# pidplate-mk-1.net
KiCad netlist of a schematic drawn in EAGLE
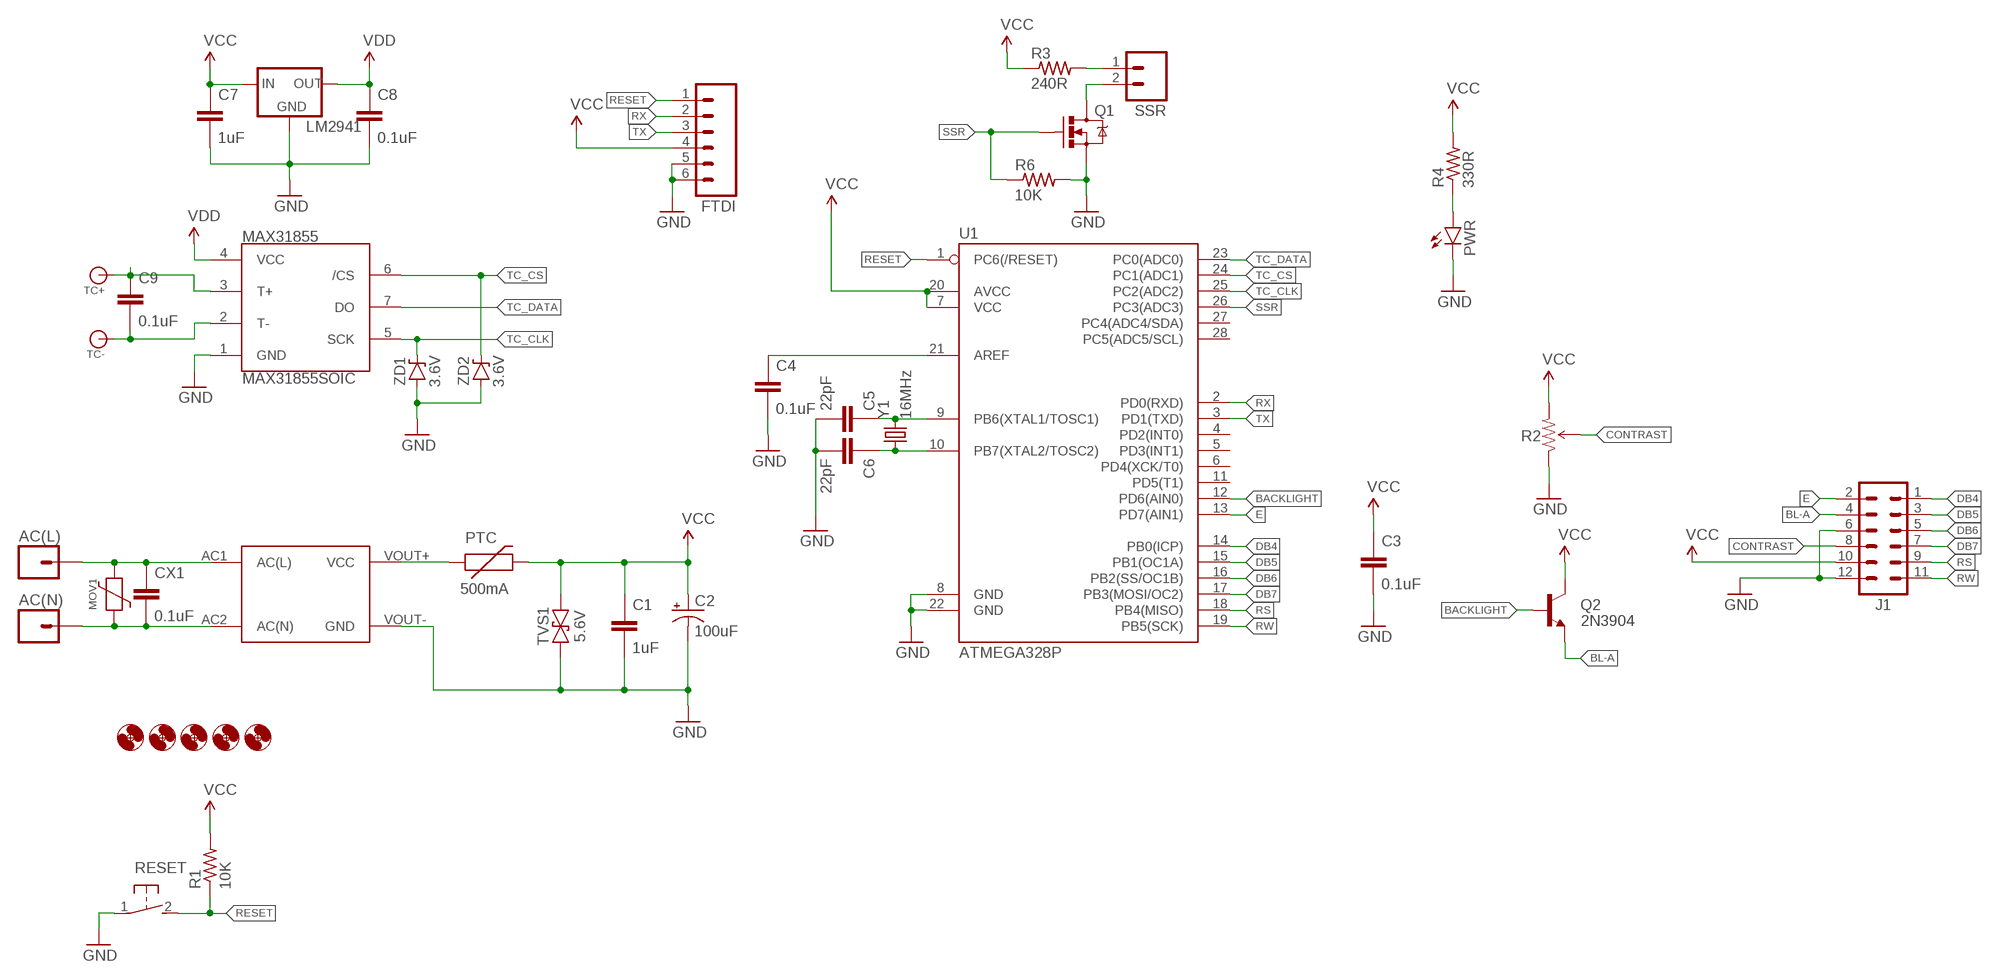
[diagram p0: schematic, sheet 1]

(export (version "E")
  (design (tool "Eeschema 10.0.6"))
  (components
    (comp (ref "AC(L)")
      (value "M01PTH-1.2MM")
      (footprint "eagle-import:1X01-1.2MM")
      (libsource (lib "eagle-import") (part "M01PTH-1.2MM"))
    )
    (comp (ref "AC(N)")
      (value "M01PTH-1.2MM")
      (footprint "eagle-import:1X01-1.2MM")
      (libsource (lib "eagle-import") (part "M01PTH-1.2MM"))
    )
    (comp (ref "C1")
      (value "1uF")
      (footprint "eagle-import:C025-024X044")
      (libsource (lib "eagle-import") (part "CAPACITOR-CERAMIC025-024X044"))
    )
    (comp (ref "C2")
      (value "100uF")
      (footprint "eagle-import:E2,5-7")
      (libsource (lib "eagle-import") (part "CAPACITOR-POLARIZEDE2.5-7"))
    )
    (comp (ref "C3")
      (value "0.1uF")
      (footprint "eagle-import:C025-024X044")
      (libsource (lib "eagle-import") (part "CAPACITOR-CERAMIC025-024X044"))
    )
    (comp (ref "C4")
      (value "0.1uF")
      (footprint "eagle-import:C025-024X044")
      (libsource (lib "eagle-import") (part "CAPACITOR-CERAMIC025-024X044"))
    )
    (comp (ref "C5")
      (value "22pF")
      (footprint "eagle-import:C025-024X044")
      (libsource (lib "eagle-import") (part "CAPACITOR-CERAMIC025-024X044"))
    )
    (comp (ref "C6")
      (value "22pF")
      (footprint "eagle-import:C025-024X044")
      (libsource (lib "eagle-import") (part "CAPACITOR-CERAMIC025-024X044"))
    )
    (comp (ref "C7")
      (value "1uF")
      (footprint "eagle-import:C025-024X044")
      (libsource (lib "eagle-import") (part "CAPACITOR-CERAMIC025-024X044"))
    )
    (comp (ref "C8")
      (value "0.1uF")
      (footprint "eagle-import:C025-024X044")
      (libsource (lib "eagle-import") (part "CAPACITOR-CERAMIC025-024X044"))
    )
    (comp (ref "C9")
      (value "0.1uF")
      (footprint "eagle-import:C025-024X044")
      (libsource (lib "eagle-import") (part "CAPACITOR-CERAMIC025-024X044"))
    )
    (comp (ref "CX1")
      (value "0.1uF")
      (footprint "eagle-import:XC10B5")
      (libsource (lib "eagle-import") (part "CXXC10B5"))
    )
    (comp (ref "FTDI")
      (value "M06SIP")
      (footprint "eagle-import:1X06")
      (libsource (lib "eagle-import") (part "M06SIP"))
    )
    (comp (ref "H1")
      (value "HOLE#2")
      (footprint "eagle-import:HOLE-#2")
      (libsource (lib "eagle-import") (part "HOLE#2"))
    )
    (comp (ref "H2")
      (value "HOLE#2")
      (footprint "eagle-import:HOLE-#2")
      (libsource (lib "eagle-import") (part "HOLE#2"))
    )
    (comp (ref "H3")
      (value "HOLE#2")
      (footprint "eagle-import:HOLE-#2")
      (libsource (lib "eagle-import") (part "HOLE#2"))
    )
    (comp (ref "H4")
      (value "HOLE#2")
      (footprint "eagle-import:HOLE-#2")
      (libsource (lib "eagle-import") (part "HOLE#2"))
    )
    (comp (ref "H5")
      (value "HOLE#2")
      (footprint "eagle-import:HOLE-#2")
      (libsource (lib "eagle-import") (part "HOLE#2"))
    )
    (comp (ref "J1")
      (value "M06X2PTH")
      (footprint "eagle-import:2X6_PTH")
      (libsource (lib "eagle-import") (part "M06X2PTH"))
    )
    (comp (ref "LM2941")
      (value "L2941")
      (footprint "eagle-import:TO-92-AMMO")
      (libsource (lib "eagle-import") (part "V_REG_78XXTO-92-INLINE"))
    )
    (comp (ref "MAX31855")
      (value "MAX31855SOIC")
      (footprint "eagle-import:SOIC127P600X175-8N")
      (libsource (lib "eagle-import") (part "MAX31855SOIC"))
    )
    (comp (ref "MOV1")
      (value "VARISITORVAR-5.08MM-PTH")
      (footprint "eagle-import:VAR-5.08MM-PTH")
      (libsource (lib "eagle-import") (part "VARISITORVAR-5.08MM-PTH"))
    )
    (comp (ref "PTC")
      (value "500mA")
      (footprint "eagle-import:PTC")
      (libsource (lib "eagle-import") (part "PTCPTH"))
    )
    (comp (ref "PWR")
      (value "LED3MM")
      (footprint "eagle-import:LED3MM")
      (libsource (lib "eagle-import") (part "LED3MM"))
    )
    (comp (ref "Q1")
      (value "2N7000")
      (footprint "eagle-import:TO-92-AMMO")
      (libsource (lib "eagle-import") (part "MOSFET-NCHANNEL2N7000-AMMO"))
    )
    (comp (ref "Q2")
      (value "2N3904")
      (footprint "eagle-import:TO-92-AMMO")
      (libsource (lib "eagle-import") (part "TRANSISTOR_NPNTO-92-AMMO-CBE"))
    )
    (comp (ref "R1")
      (value "10K")
      (footprint "eagle-import:RESISTOR-AXIAL-PTH-5.08MM")
      (libsource (lib "eagle-import") (part "RESISTORPTH-AXIAL-5.08MM"))
    )
    (comp (ref "R2")
      (value "20K")
      (footprint "eagle-import:TRIM_POT_PTH")
      (libsource (lib "eagle-import") (part "TRIMPOTPTH"))
    )
    (comp (ref "R3")
      (value "240R")
      (footprint "eagle-import:RESISTOR-AXIAL-PTH-6.35MM")
      (libsource (lib "eagle-import") (part "RESISTORPTH-AXIAL-6.35MM"))
    )
    (comp (ref "R4")
      (value "330R")
      (footprint "eagle-import:RESISTOR-AXIAL-PTH-5.08MM")
      (libsource (lib "eagle-import") (part "RESISTORPTH-AXIAL-5.08MM"))
    )
    (comp (ref "R6")
      (value "10K")
      (footprint "eagle-import:RESISTOR-AXIAL-PTH-6.35MM")
      (libsource (lib "eagle-import") (part "RESISTORPTH-AXIAL-6.35MM"))
    )
    (comp (ref "RESET")
      (value "SPST-NO-TACT3MM-RA")
      (footprint "eagle-import:TACTILE-PTH-SIDE")
      (libsource (lib "eagle-import") (part "SPST-NO-TACT3MM-RA"))
    )
    (comp (ref "SSR")
      (value "M02JST-PTH-VERT")
      (footprint "eagle-import:JST-2-PH-VERT-PTH")
      (libsource (lib "eagle-import") (part "M02JST-PTH-VERT"))
    )
    (comp (ref "TC+")
      (value "BANANA_CONNPTH-RA")
      (footprint "eagle-import:BANANA-PTH-RA-SAFEWORD")
      (libsource (lib "eagle-import") (part "BANANA_CONNPTH-RA"))
    )
    (comp (ref "TC-")
      (value "BANANA_CONNPTH-RA")
      (footprint "eagle-import:BANANA-PTH-RA-SAFEWORD")
      (libsource (lib "eagle-import") (part "BANANA_CONNPTH-RA"))
    )
    (comp (ref "TVS1")
      (value "5.6V")
      (footprint "eagle-import:DO-41-TVS")
      (libsource (lib "eagle-import") (part "TVSDO-41-TVS-BIDIRECTIONAL"))
    )
    (comp (ref "U1")
      (value "ATMEGA328P")
      (footprint "eagle-import:DIL28-3")
      (libsource (lib "eagle-import") (part "ATMEGA328P_PDIP"))
    )
    (comp (ref "U3")
      (value "VSK-S1")
      (footprint "eagle-import:VSK-S1")
      (libsource (lib "eagle-import") (part "VSK-S1"))
    )
    (comp (ref "Y1")
      (value "16MHz")
      (footprint "eagle-import:HC49U-V")
      (libsource (lib "eagle-import") (part "CRYSTALHC49UV"))
    )
    (comp (ref "ZD1")
      (value "3.6V")
      (footprint "eagle-import:DIODE-7.68MM")
      (libsource (lib "eagle-import") (part "DIODE-ZENERPTH-7.68MM"))
    )
    (comp (ref "ZD2")
      (value "3.6V")
      (footprint "eagle-import:DIODE-7.68MM")
      (libsource (lib "eagle-import") (part "DIODE-ZENERPTH-7.68MM"))
    )
  )
  (nets
    (net (code "1") (name "BACKLIGHT") (class "Default")
      (node (ref "Q2") (pin "2") (pinfunction "B_2") (pintype "passive"))
      (node (ref "U1") (pin "12") (pinfunction "PD6(AIN0)_12") (pintype "bidirectional"))
    )
    (net (code "2") (name "BL-A") (class "Default")
      (node (ref "J1") (pin "4") (pinfunction "4_4") (pintype "passive"))
      (node (ref "Q2") (pin "3") (pinfunction "E_3") (pintype "passive"))
    )
    (net (code "3") (name "CONTRAST") (class "Default")
      (node (ref "J1") (pin "8") (pinfunction "8_8") (pintype "passive"))
      (node (ref "R2") (pin "2") (pinfunction "WIPER_2") (pintype "passive"))
    )
    (net (code "4") (name "DB4") (class "Default")
      (node (ref "J1") (pin "1") (pinfunction "1_1") (pintype "passive"))
      (node (ref "U1") (pin "14") (pinfunction "PB0(ICP)_14") (pintype "bidirectional"))
    )
    (net (code "5") (name "DB5") (class "Default")
      (node (ref "J1") (pin "3") (pinfunction "3_3") (pintype "passive"))
      (node (ref "U1") (pin "15") (pinfunction "PB1(OC1A)_15") (pintype "bidirectional"))
    )
    (net (code "6") (name "DB6") (class "Default")
      (node (ref "J1") (pin "5") (pinfunction "5_5") (pintype "passive"))
      (node (ref "U1") (pin "16") (pinfunction "PB2(SS/OC1B)_16") (pintype "bidirectional"))
    )
    (net (code "7") (name "DB7") (class "Default")
      (node (ref "J1") (pin "7") (pinfunction "7_7") (pintype "passive"))
      (node (ref "U1") (pin "17") (pinfunction "PB3(MOSI/OC2)_17") (pintype "bidirectional"))
    )
    (net (code "8") (name "E") (class "Default")
      (node (ref "J1") (pin "2") (pinfunction "2_2") (pintype "passive"))
      (node (ref "U1") (pin "13") (pinfunction "PD7(AIN1)_13") (pintype "bidirectional"))
    )
    (net (code "9") (name "GND") (class "Default")
      (node (ref "C1") (pin "2") (pinfunction "2_2") (pintype "passive"))
      (node (ref "C2") (pin "-") (pinfunction "-_-") (pintype "passive"))
      (node (ref "C3") (pin "2") (pinfunction "2_2") (pintype "passive"))
      (node (ref "C4") (pin "2") (pinfunction "2_2") (pintype "passive"))
      (node (ref "C5") (pin "2") (pinfunction "2_2") (pintype "passive"))
      (node (ref "C6") (pin "2") (pinfunction "2_2") (pintype "passive"))
      (node (ref "C7") (pin "2") (pinfunction "2_2") (pintype "passive"))
      (node (ref "C8") (pin "2") (pinfunction "2_2") (pintype "passive"))
      (node (ref "FTDI") (pin "5") (pinfunction "5_5") (pintype "passive"))
      (node (ref "FTDI") (pin "6") (pinfunction "6_6") (pintype "passive"))
      (node (ref "J1") (pin "12") (pinfunction "12_12") (pintype "passive"))
      (node (ref "J1") (pin "6") (pinfunction "6_6") (pintype "passive"))
      (node (ref "LM2941") (pin "2") (pinfunction "GND_2") (pintype "input"))
      (node (ref "MAX31855") (pin "1") (pinfunction "GND_1") (pintype "power_in"))
      (node (ref "PWR") (pin "K") (pinfunction "C_K") (pintype "passive"))
      (node (ref "Q1") (pin "1") (pinfunction "S_1") (pintype "passive"))
      (node (ref "R2") (pin "1") (pinfunction "CCW_1") (pintype "passive"))
      (node (ref "R6") (pin "P$2") (pinfunction "2_P$2") (pintype "passive"))
      (node (ref "RESET") (pin "1") (pinfunction "1_1") (pintype "passive"))
      (node (ref "TVS1") (pin "P$1") (pinfunction "1_P$1") (pintype "passive"))
      (node (ref "U1") (pin "22") (pinfunction "GND_22") (pintype "bidirectional"))
      (node (ref "U1") (pin "8") (pinfunction "GND_8") (pintype "bidirectional"))
      (node (ref "U3") (pin "VOUT-") (pinfunction "GND_VOUT-") (pintype "bidirectional"))
      (node (ref "ZD1") (pin "A") (pinfunction "A_A") (pintype "passive"))
      (node (ref "ZD2") (pin "A") (pinfunction "A_A") (pintype "passive"))
    )
    (net (code "10") (name "Net-(AC(L)-1)") (class "Default")
      (node (ref "AC(L)") (pin "P$1") (pinfunction "1_P$1") (pintype "passive"))
      (node (ref "CX1") (pin "1") (pinfunction "1_1") (pintype "passive"))
      (node (ref "MOV1") (pin "2") (pinfunction "P$2_2") (pintype "bidirectional"))
      (node (ref "U3") (pin "AC1") (pinfunction "AC(L)_AC1") (pintype "bidirectional"))
    )
    (net (code "11") (name "Net-(AC(N)-1)") (class "Default")
      (node (ref "AC(N)") (pin "P$1") (pinfunction "1_P$1") (pintype "passive"))
      (node (ref "CX1") (pin "2") (pinfunction "2_2") (pintype "passive"))
      (node (ref "MOV1") (pin "1") (pinfunction "P$1_1") (pintype "bidirectional"))
      (node (ref "U3") (pin "AC2") (pinfunction "AC(N)_AC2") (pintype "bidirectional"))
    )
    (net (code "12") (name "Net-(MAX31855-T+)") (class "Default")
      (node (ref "C9") (pin "1") (pinfunction "1_1") (pintype "passive"))
      (node (ref "MAX31855") (pin "3") (pinfunction "T+_3") (pintype "input"))
      (node (ref "TC+") (pin "P$1") (pinfunction "1_P$1") (pintype "passive"))
      (node (ref "TC+") (pin "P$2") (pinfunction "1_P$2") (pintype "passive"))
    )
    (net (code "13") (name "Net-(MAX31855-T-)") (class "Default")
      (node (ref "C9") (pin "2") (pinfunction "2_2") (pintype "passive"))
      (node (ref "MAX31855") (pin "2") (pinfunction "T-_2") (pintype "input"))
      (node (ref "TC-") (pin "P$1") (pinfunction "1_P$1") (pintype "passive"))
      (node (ref "TC-") (pin "P$2") (pinfunction "1_P$2") (pintype "passive"))
    )
    (net (code "14") (name "Net-(PTC-1)") (class "Default")
      (node (ref "PTC") (pin "P$1") (pinfunction "1_P$1") (pintype "bidirectional"))
      (node (ref "U3") (pin "VOUT+") (pinfunction "VCC_VOUT+") (pintype "bidirectional"))
    )
    (net (code "15") (name "Net-(Q1-D)") (class "Default")
      (node (ref "Q1") (pin "3") (pinfunction "D_3") (pintype "passive"))
      (node (ref "SSR") (pin "2") (pinfunction "2_2") (pintype "passive"))
    )
    (net (code "16") (name "Net-(R3-2)") (class "Default")
      (node (ref "R3") (pin "P$2") (pinfunction "2_P$2") (pintype "passive"))
      (node (ref "SSR") (pin "1") (pinfunction "1_1") (pintype "passive"))
    )
    (net (code "17") (name "Net-(R4-1)") (class "Default")
      (node (ref "PWR") (pin "A") (pinfunction "A_A") (pintype "passive"))
      (node (ref "R4") (pin "P$1") (pinfunction "1_P$1") (pintype "passive"))
    )
    (net (code "18") (name "Net-(U1-AREF)") (class "Default")
      (node (ref "C4") (pin "1") (pinfunction "1_1") (pintype "passive"))
      (node (ref "U1") (pin "21") (pinfunction "AREF_21") (pintype "bidirectional"))
    )
    (net (code "19") (name "Net-(U1-PB6(XTAL1{slash}TOSC1))") (class "Default")
      (node (ref "C5") (pin "1") (pinfunction "1_1") (pintype "passive"))
      (node (ref "U1") (pin "9") (pinfunction "PB6(XTAL1/TOSC1)_9") (pintype "bidirectional"))
      (node (ref "Y1") (pin "2") (pinfunction "2_2") (pintype "passive"))
    )
    (net (code "20") (name "Net-(U1-PB7(XTAL2{slash}TOSC2))") (class "Default")
      (node (ref "C6") (pin "1") (pinfunction "1_1") (pintype "passive"))
      (node (ref "U1") (pin "10") (pinfunction "PB7(XTAL2/TOSC2)_10") (pintype "bidirectional"))
      (node (ref "Y1") (pin "1") (pinfunction "1_1") (pintype "passive"))
    )
    (net (code "21") (name "RESET") (class "Default")
      (node (ref "FTDI") (pin "1") (pinfunction "1_1") (pintype "passive"))
      (node (ref "R1") (pin "P$1") (pinfunction "1_P$1") (pintype "passive"))
      (node (ref "RESET") (pin "2") (pinfunction "2_2") (pintype "passive"))
      (node (ref "U1") (pin "1") (pinfunction "PC6(/RESET)_1") (pintype "bidirectional"))
    )
    (net (code "22") (name "RS") (class "Default")
      (node (ref "J1") (pin "9") (pinfunction "9_9") (pintype "passive"))
      (node (ref "U1") (pin "18") (pinfunction "PB4(MISO)_18") (pintype "bidirectional"))
    )
    (net (code "23") (name "RW") (class "Default")
      (node (ref "J1") (pin "11") (pinfunction "11_11") (pintype "passive"))
      (node (ref "U1") (pin "19") (pinfunction "PB5(SCK)_19") (pintype "bidirectional"))
    )
    (net (code "24") (name "RX") (class "Default")
      (node (ref "FTDI") (pin "2") (pinfunction "2_2") (pintype "passive"))
      (node (ref "U1") (pin "2") (pinfunction "PD0(RXD)_2") (pintype "bidirectional"))
    )
    (net (code "25") (name "SSR") (class "Default")
      (node (ref "Q1") (pin "2") (pinfunction "G_2") (pintype "passive"))
      (node (ref "R6") (pin "P$1") (pinfunction "1_P$1") (pintype "passive"))
      (node (ref "U1") (pin "26") (pinfunction "PC3(ADC3)_26") (pintype "bidirectional"))
    )
    (net (code "26") (name "TC_CLK") (class "Default")
      (node (ref "MAX31855") (pin "5") (pinfunction "SCK_5") (pintype "input"))
      (node (ref "U1") (pin "25") (pinfunction "PC2(ADC2)_25") (pintype "bidirectional"))
      (node (ref "ZD1") (pin "K") (pinfunction "C_K") (pintype "passive"))
    )
    (net (code "27") (name "TC_CS") (class "Default")
      (node (ref "MAX31855") (pin "6") (pinfunction "/CS_6") (pintype "input"))
      (node (ref "U1") (pin "24") (pinfunction "PC1(ADC1)_24") (pintype "bidirectional"))
      (node (ref "ZD2") (pin "K") (pinfunction "C_K") (pintype "passive"))
    )
    (net (code "28") (name "TC_DATA") (class "Default")
      (node (ref "MAX31855") (pin "7") (pinfunction "DO_7") (pintype "output"))
      (node (ref "U1") (pin "23") (pinfunction "PC0(ADC0)_23") (pintype "bidirectional"))
    )
    (net (code "29") (name "TX") (class "Default")
      (node (ref "FTDI") (pin "3") (pinfunction "3_3") (pintype "passive"))
      (node (ref "U1") (pin "3") (pinfunction "PD1(TXD)_3") (pintype "bidirectional"))
    )
    (net (code "30") (name "VCC") (class "Default")
      (node (ref "C1") (pin "1") (pinfunction "1_1") (pintype "passive"))
      (node (ref "C2") (pin "+") (pinfunction "+_+") (pintype "passive"))
      (node (ref "C3") (pin "1") (pinfunction "1_1") (pintype "passive"))
      (node (ref "C7") (pin "1") (pinfunction "1_1") (pintype "passive"))
      (node (ref "FTDI") (pin "4") (pinfunction "4_4") (pintype "passive"))
      (node (ref "J1") (pin "10") (pinfunction "10_10") (pintype "passive"))
      (node (ref "LM2941") (pin "1") (pinfunction "IN_1") (pintype "input"))
      (node (ref "PTC") (pin "P$2") (pinfunction "2_P$2") (pintype "bidirectional"))
      (node (ref "Q2") (pin "1") (pinfunction "C_1") (pintype "passive"))
      (node (ref "R1") (pin "P$2") (pinfunction "2_P$2") (pintype "passive"))
      (node (ref "R2") (pin "3") (pinfunction "CW_3") (pintype "passive"))
      (node (ref "R3") (pin "P$1") (pinfunction "1_P$1") (pintype "passive"))
      (node (ref "R4") (pin "P$2") (pinfunction "2_P$2") (pintype "passive"))
      (node (ref "TVS1") (pin "P$2") (pinfunction "2_P$2") (pintype "passive"))
      (node (ref "U1") (pin "20") (pinfunction "AVCC_20") (pintype "bidirectional"))
      (node (ref "U1") (pin "7") (pinfunction "VCC_7") (pintype "bidirectional"))
    )
    (net (code "31") (name "VDD") (class "Default")
      (node (ref "C8") (pin "1") (pinfunction "1_1") (pintype "passive"))
      (node (ref "LM2941") (pin "3") (pinfunction "OUT_3") (pintype "output"))
      (node (ref "MAX31855") (pin "4") (pinfunction "VCC_4") (pintype "power_in"))
    )
    (net (code "32") (name "unconnected-(U1-PC4(ADC4{slash}SDA)-Pad27)") (class "Default")
      (node (ref "U1") (pin "27") (pinfunction "PC4(ADC4/SDA)_27") (pintype "bidirectional"))
    )
    (net (code "33") (name "unconnected-(U1-PC5(ADC5{slash}SCL)-Pad28)") (class "Default")
      (node (ref "U1") (pin "28") (pinfunction "PC5(ADC5/SCL)_28") (pintype "bidirectional"))
    )
    (net (code "34") (name "unconnected-(U1-PD2(INT0)-Pad4)") (class "Default")
      (node (ref "U1") (pin "4") (pinfunction "PD2(INT0)_4") (pintype "bidirectional"))
    )
    (net (code "35") (name "unconnected-(U1-PD3(INT1)-Pad5)") (class "Default")
      (node (ref "U1") (pin "5") (pinfunction "PD3(INT1)_5") (pintype "bidirectional"))
    )
    (net (code "36") (name "unconnected-(U1-PD4(XCK{slash}T0)-Pad6)") (class "Default")
      (node (ref "U1") (pin "6") (pinfunction "PD4(XCK/T0)_6") (pintype "bidirectional"))
    )
    (net (code "37") (name "unconnected-(U1-PD5(T1)-Pad11)") (class "Default")
      (node (ref "U1") (pin "11") (pinfunction "PD5(T1)_11") (pintype "bidirectional"))
    )
  )
)
